# Nexmonitor_Invasivo.net
KiCad netlist of a schematic drawn in EAGLE
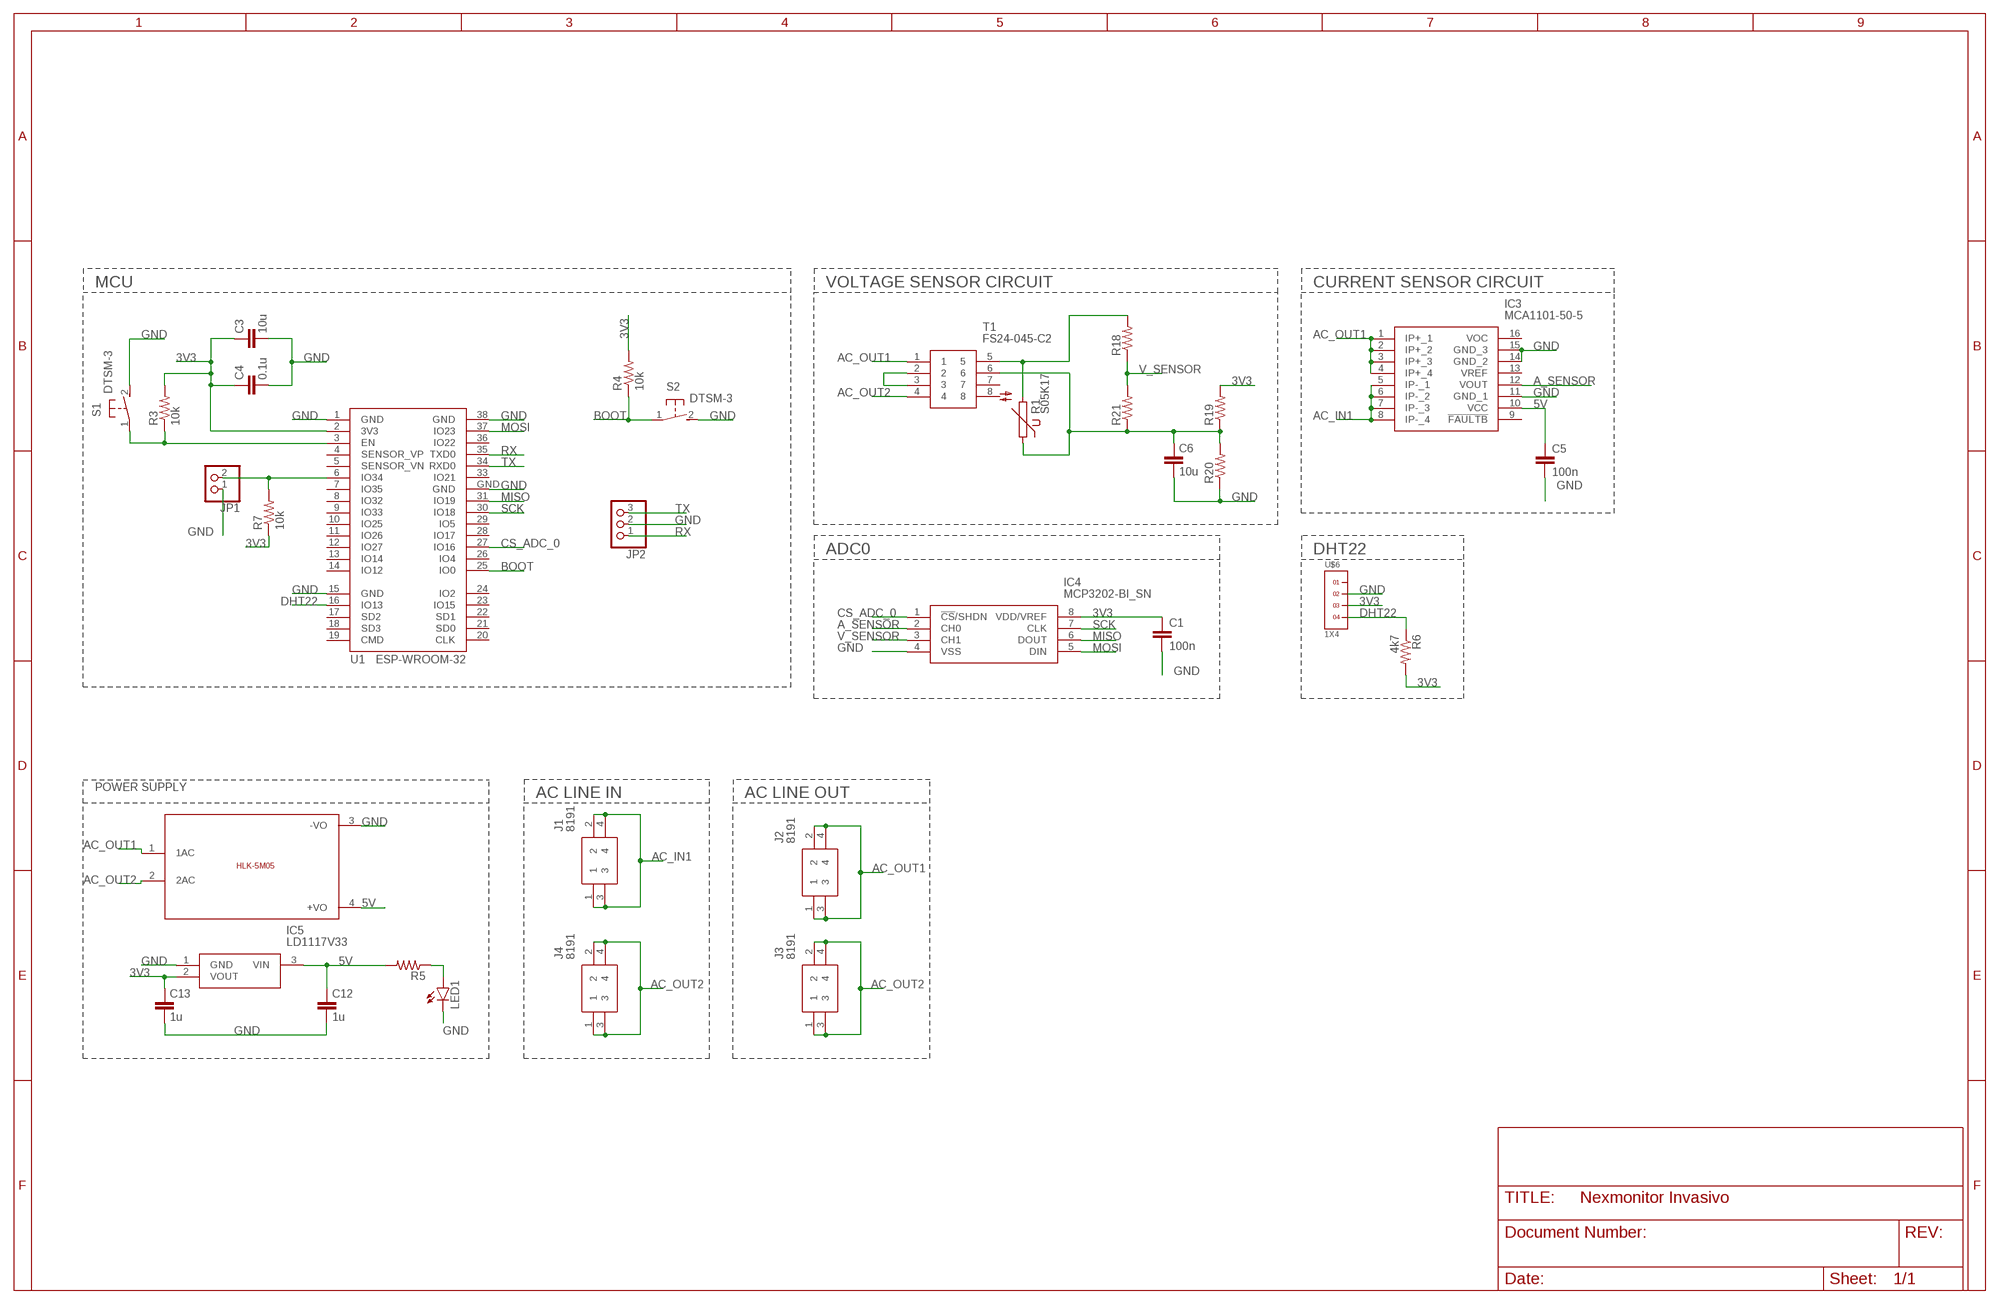
[diagram p0: schematic, sheet 1]

(export (version "E")
  (design (tool "Eeschema 10.0.6"))
  (components
    (comp (ref "C1")
      (value "100n")
      (footprint "eagle-import:C0805K")
      (libsource (lib "eagle-import") (part "C-EUC0805K"))
    )
    (comp (ref "C3")
      (value "10u")
      (footprint "eagle-import:C0805")
      (libsource (lib "eagle-import") (part "C-EUC0805"))
    )
    (comp (ref "C4")
      (value "0.1u")
      (footprint "eagle-import:C0805")
      (libsource (lib "eagle-import") (part "C-EUC0805"))
    )
    (comp (ref "C5")
      (value "100n")
      (footprint "eagle-import:C0805K")
      (libsource (lib "eagle-import") (part "C-EUC0805K"))
    )
    (comp (ref "C6")
      (value "10u")
      (footprint "eagle-import:C0805")
      (libsource (lib "eagle-import") (part "C-EUC0805"))
    )
    (comp (ref "C12")
      (value "1u")
      (footprint "eagle-import:C025-025X050")
      (libsource (lib "eagle-import") (part "C-EU025-025X050"))
    )
    (comp (ref "C13")
      (value "1u")
      (footprint "eagle-import:C025-025X050")
      (libsource (lib "eagle-import") (part "C-EU025-025X050"))
    )
    (comp (ref "IC3")
      (value "MCA1101-50-5")
      (footprint "eagle-import:SOIC127P1031X264-16N")
      (fields (field (name "MOUSER_PART_NUMBER") "438-MCA1101-50-5"))
      (libsource (lib "eagle-import") (part "MCA1101-50-5"))
    )
    (comp (ref "IC4")
      (value "MCP3202-BI_SN")
      (footprint "eagle-import:SOIC127P600X175-8N")
      (fields
        (field (name "MANUFACTURER_PART_NUMBER") "MCP3202-BI/SN")
        (field (name "MOUSER_PART_NUMBER") "579-MCP3202BISN")
      )
      (libsource (lib "eagle-import") (part "MCP3202-BI_SN"))
    )
    (comp (ref "IC5")
      (value "LD1117V33")
      (footprint "eagle-import:TO270P460X1020X2008-3P")
      (fields (field (name "MOUSER_PART_NUMBER") "511-LD1117V33"))
      (libsource (lib "eagle-import") (part "LD1117V33"))
    )
    (comp (ref "J1")
      (value "8191")
      (footprint "eagle-import:8191")
      (fields (field (name "MOUSER_PART_NUMBER") "534-8191"))
      (libsource (lib "eagle-import") (part "8191"))
    )
    (comp (ref "J2")
      (value "8191")
      (footprint "eagle-import:8191")
      (fields (field (name "MOUSER_PART_NUMBER") "534-8191"))
      (libsource (lib "eagle-import") (part "8191"))
    )
    (comp (ref "J3")
      (value "8191")
      (footprint "eagle-import:8191")
      (fields (field (name "MOUSER_PART_NUMBER") "534-8191"))
      (libsource (lib "eagle-import") (part "8191"))
    )
    (comp (ref "J4")
      (value "8191")
      (footprint "eagle-import:8191")
      (fields (field (name "MOUSER_PART_NUMBER") "534-8191"))
      (libsource (lib "eagle-import") (part "8191"))
    )
    (comp (ref "JP1")
      (value "PINHD-1X2")
      (footprint "eagle-import:1X02")
      (libsource (lib "eagle-import") (part "PINHD-1X2"))
    )
    (comp (ref "JP2")
      (value "PINHD-1X3")
      (footprint "eagle-import:1X03")
      (libsource (lib "eagle-import") (part "PINHD-1X3"))
    )
    (comp (ref "LED1")
      (value "LED5MM")
      (footprint "eagle-import:LED5MM")
      (libsource (lib "eagle-import") (part "LED5MM"))
    )
    (comp (ref "R1")
      (value "S05K17")
      (footprint "eagle-import:S05K17")
      (libsource (lib "eagle-import") (part "S05K17"))
    )
    (comp (ref "R3")
      (value "10k")
      (footprint "eagle-import:R0805")
      (libsource (lib "eagle-import") (part "R-US_R0805"))
    )
    (comp (ref "R4")
      (value "10k")
      (footprint "eagle-import:R0805")
      (libsource (lib "eagle-import") (part "R-US_R0805"))
    )
    (comp (ref "R5")
      (value "470")
      (footprint "eagle-import:R0805")
      (libsource (lib "eagle-import") (part "R-US_R0805"))
    )
    (comp (ref "R6")
      (value "4k7")
      (footprint "eagle-import:R0805")
      (libsource (lib "eagle-import") (part "R-US_R0805"))
    )
    (comp (ref "R7")
      (value "10k")
      (footprint "eagle-import:R0805")
      (libsource (lib "eagle-import") (part "R-US_R0805"))
    )
    (comp (ref "R18")
      (value "470k")
      (footprint "eagle-import:R0805")
      (libsource (lib "eagle-import") (part "R-US_R0805"))
    )
    (comp (ref "R19")
      (value "120k")
      (footprint "eagle-import:R0805")
      (libsource (lib "eagle-import") (part "R-US_R0805"))
    )
    (comp (ref "R20")
      (value "470k")
      (footprint "eagle-import:R0805")
      (libsource (lib "eagle-import") (part "R-US_R0805"))
    )
    (comp (ref "R21")
      (value "33k")
      (footprint "eagle-import:R0805")
      (libsource (lib "eagle-import") (part "R-US_R0805"))
    )
    (comp (ref "S1")
      (value "DTSM-3")
      (footprint "eagle-import:DTSM-3")
      (libsource (lib "eagle-import") (part "DTSM-3"))
    )
    (comp (ref "S2")
      (value "DTSM-3")
      (footprint "eagle-import:DTSM-3")
      (libsource (lib "eagle-import") (part "DTSM-3"))
    )
    (comp (ref "T1")
      (value "FS24-045-C2")
      (footprint "eagle-import:FS24045C2")
      (fields (field (name "MOUSER_PART_NUMBER") "553-FS24-045-C2"))
      (libsource (lib "eagle-import") (part "FS24-045-C2"))
    )
    (comp (ref "U$5")
      (value "5VDC/5W")
      (footprint "eagle-import:HLK-5M05")
      (libsource (lib "eagle-import") (part "HLK-5M05"))
    )
    (comp (ref "U$6")
      (value "1X4")
      (footprint "eagle-import:1X4")
      (libsource (lib "eagle-import") (part "1X4"))
    )
    (comp (ref "U1")
      (value "ESP-WROOM-32")
      (footprint "eagle-import:ESP-WROOM-32")
      (libsource (lib "eagle-import") (part "ESP-WROOM-32"))
    )
  )
  (nets
    (net (code "1") (name "/3V3") (class "Default")
      (node (ref "C1") (pin "1") (pinfunction "1_1") (pintype "passive"))
      (node (ref "C13") (pin "1") (pinfunction "1_1") (pintype "passive"))
      (node (ref "C3") (pin "1") (pinfunction "1_1") (pintype "passive"))
      (node (ref "C4") (pin "1") (pinfunction "1_1") (pintype "passive"))
      (node (ref "IC4") (pin "8") (pinfunction "VDD/VREF_8") (pintype "power_in"))
      (node (ref "IC5") (pin "2") (pinfunction "VOUT_2") (pintype "output"))
      (node (ref "R19") (pin "2") (pinfunction "2_2") (pintype "passive"))
      (node (ref "R3") (pin "2") (pinfunction "2_2") (pintype "passive"))
      (node (ref "R4") (pin "2") (pinfunction "2_2") (pintype "passive"))
      (node (ref "R6") (pin "2") (pinfunction "2_2") (pintype "passive"))
      (node (ref "R7") (pin "1") (pinfunction "1_1") (pintype "passive"))
      (node (ref "U$6") (pin "3") (pinfunction "3_3") (pintype "bidirectional"))
      (node (ref "U1") (pin "2") (pinfunction "3V3_2") (pintype "power_in"))
    )
    (net (code "2") (name "/5V") (class "Default")
      (node (ref "C12") (pin "1") (pinfunction "1_1") (pintype "passive"))
      (node (ref "C5") (pin "1") (pinfunction "1_1") (pintype "passive"))
      (node (ref "IC3") (pin "10") (pinfunction "VCC_10") (pintype "bidirectional"))
      (node (ref "IC5") (pin "3") (pinfunction "VIN_3") (pintype "input"))
      (node (ref "R5") (pin "2") (pinfunction "2_2") (pintype "passive"))
      (node (ref "U$5") (pin "4") (pinfunction "+VO_4") (pintype "bidirectional"))
    )
    (net (code "3") (name "/AC_IN1") (class "Default")
      (node (ref "IC3") (pin "5") (pinfunction "IP-_1_5") (pintype "bidirectional"))
      (node (ref "IC3") (pin "6") (pinfunction "IP-_2_6") (pintype "bidirectional"))
      (node (ref "IC3") (pin "7") (pinfunction "IP-_3_7") (pintype "bidirectional"))
      (node (ref "IC3") (pin "8") (pinfunction "IP-_4_8") (pintype "bidirectional"))
      (node (ref "J1") (pin "1") (pinfunction "1_1") (pintype "bidirectional"))
      (node (ref "J1") (pin "2") (pinfunction "2_2") (pintype "bidirectional"))
      (node (ref "J1") (pin "3") (pinfunction "3_3") (pintype "bidirectional"))
      (node (ref "J1") (pin "4") (pinfunction "4_4") (pintype "bidirectional"))
    )
    (net (code "4") (name "/AC_OUT1") (class "Default")
      (node (ref "IC3") (pin "1") (pinfunction "IP+_1_1") (pintype "bidirectional"))
      (node (ref "IC3") (pin "2") (pinfunction "IP+_2_2") (pintype "bidirectional"))
      (node (ref "IC3") (pin "3") (pinfunction "IP+_3_3") (pintype "bidirectional"))
      (node (ref "IC3") (pin "4") (pinfunction "IP+_4_4") (pintype "bidirectional"))
      (node (ref "J2") (pin "1") (pinfunction "1_1") (pintype "bidirectional"))
      (node (ref "J2") (pin "2") (pinfunction "2_2") (pintype "bidirectional"))
      (node (ref "J2") (pin "3") (pinfunction "3_3") (pintype "bidirectional"))
      (node (ref "J2") (pin "4") (pinfunction "4_4") (pintype "bidirectional"))
      (node (ref "T1") (pin "1") (pinfunction "1_1") (pintype "bidirectional"))
      (node (ref "U$5") (pin "1") (pinfunction "1AC_1") (pintype "bidirectional"))
    )
    (net (code "5") (name "/AC_OUT2") (class "Default")
      (node (ref "J3") (pin "1") (pinfunction "1_1") (pintype "bidirectional"))
      (node (ref "J3") (pin "2") (pinfunction "2_2") (pintype "bidirectional"))
      (node (ref "J3") (pin "3") (pinfunction "3_3") (pintype "bidirectional"))
      (node (ref "J3") (pin "4") (pinfunction "4_4") (pintype "bidirectional"))
      (node (ref "J4") (pin "1") (pinfunction "1_1") (pintype "bidirectional"))
      (node (ref "J4") (pin "2") (pinfunction "2_2") (pintype "bidirectional"))
      (node (ref "J4") (pin "3") (pinfunction "3_3") (pintype "bidirectional"))
      (node (ref "J4") (pin "4") (pinfunction "4_4") (pintype "bidirectional"))
      (node (ref "T1") (pin "4") (pinfunction "4_4") (pintype "bidirectional"))
      (node (ref "U$5") (pin "2") (pinfunction "2AC_2") (pintype "bidirectional"))
    )
    (net (code "6") (name "/A_SENSOR") (class "Default")
      (node (ref "IC3") (pin "12") (pinfunction "VOUT_12") (pintype "bidirectional"))
      (node (ref "IC4") (pin "2") (pinfunction "CH0_2") (pintype "bidirectional"))
    )
    (net (code "7") (name "/BOOT") (class "Default")
      (node (ref "R4") (pin "1") (pinfunction "1_1") (pintype "passive"))
      (node (ref "S2") (pin "1") (pinfunction "1_1") (pintype "passive"))
      (node (ref "U1") (pin "25") (pinfunction "IO0_25") (pintype "bidirectional"))
    )
    (net (code "8") (name "/CS_ADC_0") (class "Default")
      (node (ref "IC4") (pin "1") (pinfunction "~{CS}/SHDN_1") (pintype "input"))
      (node (ref "U1") (pin "27") (pinfunction "IO16_27") (pintype "bidirectional"))
    )
    (net (code "9") (name "/DHT22") (class "Default")
      (node (ref "R6") (pin "1") (pinfunction "1_1") (pintype "passive"))
      (node (ref "U$6") (pin "4") (pinfunction "4_4") (pintype "bidirectional"))
      (node (ref "U1") (pin "16") (pinfunction "IO13_16") (pintype "bidirectional"))
    )
    (net (code "10") (name "/GND") (class "Default")
      (node (ref "C1") (pin "2") (pinfunction "2_2") (pintype "passive"))
      (node (ref "C12") (pin "2") (pinfunction "2_2") (pintype "passive"))
      (node (ref "C13") (pin "2") (pinfunction "2_2") (pintype "passive"))
      (node (ref "C3") (pin "2") (pinfunction "2_2") (pintype "passive"))
      (node (ref "C4") (pin "2") (pinfunction "2_2") (pintype "passive"))
      (node (ref "C5") (pin "2") (pinfunction "2_2") (pintype "passive"))
      (node (ref "C6") (pin "2") (pinfunction "2_2") (pintype "passive"))
      (node (ref "IC3") (pin "11") (pinfunction "GND_1_11") (pintype "bidirectional"))
      (node (ref "IC3") (pin "14") (pinfunction "GND_2_14") (pintype "bidirectional"))
      (node (ref "IC3") (pin "15") (pinfunction "GND_3_15") (pintype "bidirectional"))
      (node (ref "IC4") (pin "4") (pinfunction "VSS_4") (pintype "power_in"))
      (node (ref "IC5") (pin "1") (pinfunction "GND_1") (pintype "power_in"))
      (node (ref "JP1") (pin "1") (pinfunction "1_1") (pintype "passive"))
      (node (ref "JP2") (pin "2") (pinfunction "2_2") (pintype "passive"))
      (node (ref "LED1") (pin "K") (pinfunction "C_K") (pintype "passive"))
      (node (ref "R20") (pin "1") (pinfunction "1_1") (pintype "passive"))
      (node (ref "S1") (pin "2") (pinfunction "2_2") (pintype "passive"))
      (node (ref "S2") (pin "2") (pinfunction "2_2") (pintype "passive"))
      (node (ref "U$5") (pin "3") (pinfunction "-VO_3") (pintype "bidirectional"))
      (node (ref "U$6") (pin "2") (pinfunction "2_2") (pintype "bidirectional"))
      (node (ref "U1") (pin "1") (pinfunction "GND_1") (pintype "power_in"))
      (node (ref "U1") (pin "15") (pinfunction "GND_15") (pintype "power_in"))
      (node (ref "U1") (pin "38") (pinfunction "GND_38") (pintype "power_in"))
      (node (ref "U1") (pin "GND") (pinfunction "GND_GND") (pintype "power_in"))
    )
    (net (code "11") (name "/MISO") (class "Default")
      (node (ref "IC4") (pin "6") (pinfunction "DOUT_6") (pintype "output"))
      (node (ref "U1") (pin "31") (pinfunction "IO19_31") (pintype "bidirectional"))
    )
    (net (code "12") (name "/MOSI") (class "Default")
      (node (ref "IC4") (pin "5") (pinfunction "DIN_5") (pintype "input"))
      (node (ref "U1") (pin "37") (pinfunction "IO23_37") (pintype "bidirectional"))
    )
    (net (code "13") (name "/RX") (class "Default")
      (node (ref "JP2") (pin "1") (pinfunction "1_1") (pintype "passive"))
      (node (ref "U1") (pin "35") (pinfunction "TXD0_35") (pintype "bidirectional"))
    )
    (net (code "14") (name "/SCK") (class "Default")
      (node (ref "IC4") (pin "7") (pinfunction "CLK_7") (pintype "input"))
      (node (ref "U1") (pin "30") (pinfunction "IO18_30") (pintype "bidirectional"))
    )
    (net (code "15") (name "/TX") (class "Default")
      (node (ref "JP2") (pin "3") (pinfunction "3_3") (pintype "passive"))
      (node (ref "U1") (pin "34") (pinfunction "RXD0_34") (pintype "bidirectional"))
    )
    (net (code "16") (name "/V_SENSOR") (class "Default")
      (node (ref "IC4") (pin "3") (pinfunction "CH1_3") (pintype "bidirectional"))
      (node (ref "R18") (pin "1") (pinfunction "1_1") (pintype "passive"))
      (node (ref "R21") (pin "2") (pinfunction "2_2") (pintype "passive"))
    )
    (net (code "17") (name "Net-(C6-Pad1)") (class "Default")
      (node (ref "C6") (pin "1") (pinfunction "1_1") (pintype "passive"))
      (node (ref "R1") (pin "1") (pinfunction "1_1") (pintype "passive"))
      (node (ref "R19") (pin "1") (pinfunction "1_1") (pintype "passive"))
      (node (ref "R20") (pin "2") (pinfunction "2_2") (pintype "passive"))
      (node (ref "R21") (pin "1") (pinfunction "1_1") (pintype "passive"))
      (node (ref "T1") (pin "6") (pinfunction "6_6") (pintype "bidirectional"))
    )
    (net (code "18") (name "Net-(LED1-PadA)") (class "Default")
      (node (ref "LED1") (pin "A") (pinfunction "A_A") (pintype "passive"))
      (node (ref "R5") (pin "1") (pinfunction "1_1") (pintype "passive"))
    )
    (net (code "19") (name "Net-(R1-Pad2)") (class "Default")
      (node (ref "R1") (pin "2") (pinfunction "2_2") (pintype "passive"))
      (node (ref "R18") (pin "2") (pinfunction "2_2") (pintype "passive"))
      (node (ref "T1") (pin "5") (pinfunction "5_5") (pintype "bidirectional"))
    )
    (net (code "20") (name "Net-(T1-Pad2)") (class "Default")
      (node (ref "T1") (pin "2") (pinfunction "2_2") (pintype "bidirectional"))
      (node (ref "T1") (pin "3") (pinfunction "3_3") (pintype "bidirectional"))
    )
    (net (code "21") (name "Net-(U1-EN)") (class "Default")
      (node (ref "R3") (pin "1") (pinfunction "1_1") (pintype "passive"))
      (node (ref "S1") (pin "1") (pinfunction "1_1") (pintype "passive"))
      (node (ref "U1") (pin "3") (pinfunction "EN_3") (pintype "input"))
    )
    (net (code "22") (name "Net-(U1-IO34)") (class "Default")
      (node (ref "JP1") (pin "2") (pinfunction "2_2") (pintype "passive"))
      (node (ref "R7") (pin "2") (pinfunction "2_2") (pintype "passive"))
      (node (ref "U1") (pin "6") (pinfunction "IO34_6") (pintype "bidirectional"))
    )
    (net (code "23") (name "unconnected-(IC3-VOC-Pad16)") (class "Default")
      (node (ref "IC3") (pin "16") (pinfunction "VOC_16") (pintype "bidirectional"))
    )
    (net (code "24") (name "unconnected-(IC3-VREF-Pad13)") (class "Default")
      (node (ref "IC3") (pin "13") (pinfunction "VREF_13") (pintype "bidirectional"))
    )
    (net (code "25") (name "unconnected-(IC3-~{FAULTB}-Pad9)") (class "Default")
      (node (ref "IC3") (pin "9") (pinfunction "~{FAULTB}_9") (pintype "bidirectional"))
    )
    (net (code "26") (name "unconnected-(T1-Pad7)") (class "Default")
      (node (ref "T1") (pin "7") (pinfunction "7_7") (pintype "bidirectional"))
    )
    (net (code "27") (name "unconnected-(T1-Pad8)") (class "Default")
      (node (ref "T1") (pin "8") (pinfunction "8_8") (pintype "bidirectional"))
    )
    (net (code "28") (name "unconnected-(U$6-Pad1)") (class "Default")
      (node (ref "U$6") (pin "1") (pinfunction "1_1") (pintype "bidirectional"))
    )
    (net (code "29") (name "unconnected-(U1-CLK-Pad20)") (class "Default")
      (node (ref "U1") (pin "20") (pinfunction "CLK_20") (pintype "bidirectional"))
    )
    (net (code "30") (name "unconnected-(U1-CMD-Pad19)") (class "Default")
      (node (ref "U1") (pin "19") (pinfunction "CMD_19") (pintype "bidirectional"))
    )
    (net (code "31") (name "unconnected-(U1-IO2-Pad24)") (class "Default")
      (node (ref "U1") (pin "24") (pinfunction "IO2_24") (pintype "bidirectional"))
    )
    (net (code "32") (name "unconnected-(U1-IO4-Pad26)") (class "Default")
      (node (ref "U1") (pin "26") (pinfunction "IO4_26") (pintype "bidirectional"))
    )
    (net (code "33") (name "unconnected-(U1-IO5-Pad29)") (class "Default")
      (node (ref "U1") (pin "29") (pinfunction "IO5_29") (pintype "bidirectional"))
    )
    (net (code "34") (name "unconnected-(U1-IO12-Pad14)") (class "Default")
      (node (ref "U1") (pin "14") (pinfunction "IO12_14") (pintype "bidirectional"))
    )
    (net (code "35") (name "unconnected-(U1-IO14-Pad13)") (class "Default")
      (node (ref "U1") (pin "13") (pinfunction "IO14_13") (pintype "bidirectional"))
    )
    (net (code "36") (name "unconnected-(U1-IO15-Pad23)") (class "Default")
      (node (ref "U1") (pin "23") (pinfunction "IO15_23") (pintype "bidirectional"))
    )
    (net (code "37") (name "unconnected-(U1-IO17-Pad28)") (class "Default")
      (node (ref "U1") (pin "28") (pinfunction "IO17_28") (pintype "bidirectional"))
    )
    (net (code "38") (name "unconnected-(U1-IO21-Pad33)") (class "Default")
      (node (ref "U1") (pin "33") (pinfunction "IO21_33") (pintype "bidirectional"))
    )
    (net (code "39") (name "unconnected-(U1-IO22-Pad36)") (class "Default")
      (node (ref "U1") (pin "36") (pinfunction "IO22_36") (pintype "bidirectional"))
    )
    (net (code "40") (name "unconnected-(U1-IO25-Pad10)") (class "Default")
      (node (ref "U1") (pin "10") (pinfunction "IO25_10") (pintype "bidirectional"))
    )
    (net (code "41") (name "unconnected-(U1-IO26-Pad11)") (class "Default")
      (node (ref "U1") (pin "11") (pinfunction "IO26_11") (pintype "bidirectional"))
    )
    (net (code "42") (name "unconnected-(U1-IO27-Pad12)") (class "Default")
      (node (ref "U1") (pin "12") (pinfunction "IO27_12") (pintype "bidirectional"))
    )
    (net (code "43") (name "unconnected-(U1-IO32-Pad8)") (class "Default")
      (node (ref "U1") (pin "8") (pinfunction "IO32_8") (pintype "bidirectional"))
    )
    (net (code "44") (name "unconnected-(U1-IO33-Pad9)") (class "Default")
      (node (ref "U1") (pin "9") (pinfunction "IO33_9") (pintype "bidirectional"))
    )
    (net (code "45") (name "unconnected-(U1-IO35-Pad7)") (class "Default")
      (node (ref "U1") (pin "7") (pinfunction "IO35_7") (pintype "bidirectional"))
    )
    (net (code "46") (name "unconnected-(U1-SD0-Pad21)") (class "Default")
      (node (ref "U1") (pin "21") (pinfunction "SD0_21") (pintype "bidirectional"))
    )
    (net (code "47") (name "unconnected-(U1-SD1-Pad22)") (class "Default")
      (node (ref "U1") (pin "22") (pinfunction "SD1_22") (pintype "bidirectional"))
    )
    (net (code "48") (name "unconnected-(U1-SD2-Pad17)") (class "Default")
      (node (ref "U1") (pin "17") (pinfunction "SD2_17") (pintype "bidirectional"))
    )
    (net (code "49") (name "unconnected-(U1-SD3-Pad18)") (class "Default")
      (node (ref "U1") (pin "18") (pinfunction "SD3_18") (pintype "bidirectional"))
    )
    (net (code "50") (name "unconnected-(U1-SENSOR_VN-Pad5)") (class "Default")
      (node (ref "U1") (pin "5") (pinfunction "SENSOR_VN_5") (pintype "bidirectional"))
    )
    (net (code "51") (name "unconnected-(U1-SENSOR_VP-Pad4)") (class "Default")
      (node (ref "U1") (pin "4") (pinfunction "SENSOR_VP_4") (pintype "bidirectional"))
    )
  )
)
